# dk_binh_nuoc_nong.net
KiCad netlist of a schematic drawn in Altium Designer
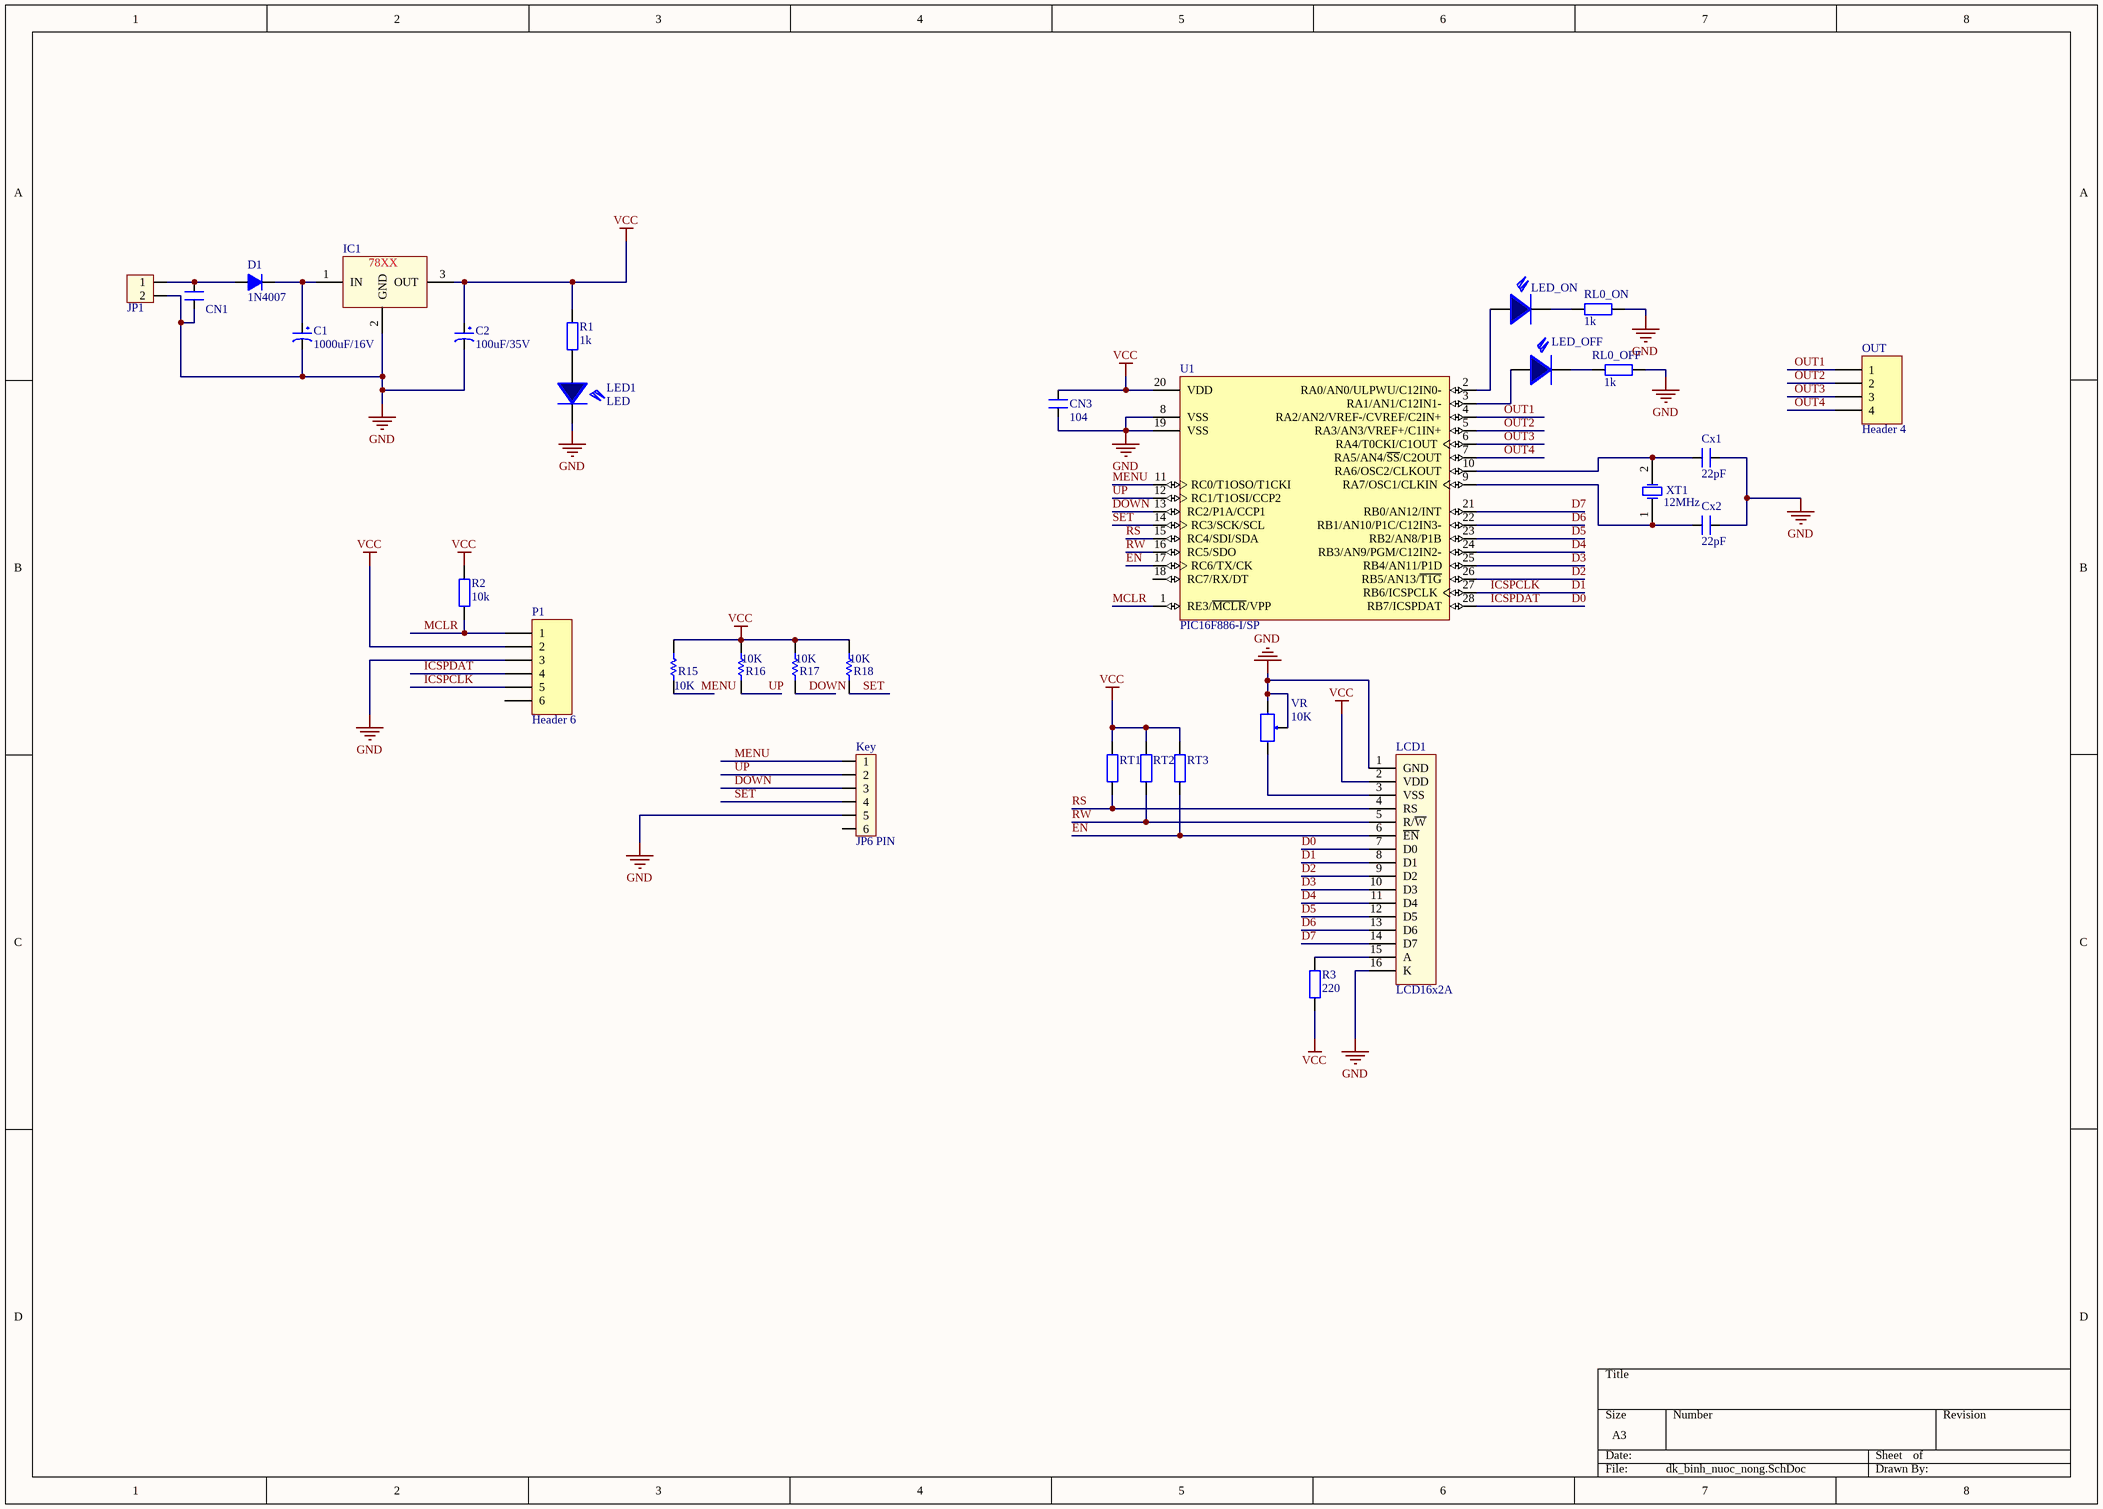
[diagram p0: dk_binh_nuoc_nong.SchDoc]

(export (version "E")
  (design (tool "Eeschema 10.0.6"))
  (components
    (comp (ref "C1")
      (value "1000uF/16V")
      (footprint "CP1.5/3.4")
      (description "Cap 1000uF/16V - 220uF/50V")
      (libsource (lib "Duy_Schematic") (part "CP4"))
    )
    (comp (ref "C2")
      (value "100uF/35V")
      (footprint "CP1.5/3.4")
      (description "Cap 100uF/35V - 470uF/16V")
      (libsource (lib "Duy_Schematic") (part "CP3"))
    )
    (comp (ref "CN1")
      (value "104")
      (footprint "CN1")
      (description "Cap np Cremic Value  104pF => 105pF")
      (libsource (lib "Duy_Schematic") (part "CN2"))
    )
    (comp (ref "CN3")
      (value "104")
      (footprint "CN1")
      (description "Cap np Cremic Value  104pF => 105pF")
      (libsource (lib "Duy_Schematic") (part "CN2"))
    )
    (comp (ref "Cx1")
      (value "22pF")
      (footprint "CN1")
      (description "Cap np Cremic value 1pF => 100pF")
      (libsource (lib "Duy_Schematic") (part "CN0"))
    )
    (comp (ref "Cx2")
      (value "22pF")
      (footprint "CN1")
      (description "Cap np Cremic value 1pF => 100pF")
      (libsource (lib "Duy_Schematic") (part "CN0"))
    )
    (comp (ref "D1")
      (value "1N4007")
      (footprint "D1A")
      (description "Diode 1A")
      (libsource (lib "Duy_Schematic") (part "D1A"))
    )
    (comp (ref "IC1") (value "78xx") (footprint "QTO-220") (libsource (lib "Duy_Schematic") (part "78xx")))
    (comp (ref "JP1")
      (value "JP2")
      (footprint "CON2")
      (description "Connector 2")
      (libsource (lib "Duy_Schematic") (part "Con2"))
    )
    (comp (ref "Key") (value "JP6 PIN") (footprint "JP6") (libsource (lib "Duy_Schematic") (part "JP6")))
    (comp (ref "LCD1")
      (value "LCD16x2A")
      (footprint "LCD16X2")
      (description "LCD dipslay 16 char, 2 line")
      (libsource (lib "Duy_Schematic") (part "LCD16x2"))
    )
    (comp (ref "LED1")
      (value "LED")
      (footprint "LED-3")
      (description "Led  Vuong")
      (libsource (lib "Duy_Schematic") (part "LED"))
    )
    (comp (ref "LED_OFF")
      (value "LED")
      (footprint "LED-3")
      (description "Led  Vuong")
      (libsource (lib "Duy_Schematic") (part "LED"))
    )
    (comp (ref "LED_ON")
      (value "LED")
      (footprint "LED-3")
      (description "Led  Vuong")
      (libsource (lib "Duy_Schematic") (part "LED"))
    )
    (comp (ref "OUT")
      (value "Header 4")
      (footprint "HDR1X4")
      (description "Header, 4-Pin")
      (fields (field (name "PUBLISHER") "Altium Limited"))
      (libsource (lib "Miscellaneous Connectors") (part "Header 4"))
    )
    (comp (ref "P1")
      (value "Header 6")
      (footprint "HED6")
      (description "Header, 6-Pin")
      (fields (field (name "PUBLISHER") "Altium Limited"))
      (libsource (lib "Miscellaneous Connectors") (part "Header 6"))
    )
    (comp (ref "R1")
      (value "1k")
      (footprint "R1/4W")
      (description "Resistor 1/4W")
      (libsource (lib "Duy_Schematic") (part "R1/4W"))
    )
    (comp (ref "R2")
      (value "10k")
      (footprint "R1/4W")
      (description "Resistor 1/4W")
      (libsource (lib "Duy_Schematic") (part "R1/4W"))
    )
    (comp (ref "R3")
      (value "220")
      (footprint "R1/4W")
      (description "Resistor 1/4W")
      (libsource (lib "Duy_Schematic") (part "R1/4W"))
    )
    (comp (ref "R15")
      (value "Res")
      (footprint "Device:R_Nor")
      (fields (field (name "ALTIUM_UNNAMED_1") "10K"))
      (libsource (lib "Device") (part "Res"))
    )
    (comp (ref "R16") (value "10K") (footprint "Device:R_Nor") (libsource (lib "Device") (part "Res")))
    (comp (ref "R17") (value "10K") (footprint "Device:R_Nor") (libsource (lib "Device") (part "Res")))
    (comp (ref "R18") (value "10K") (footprint "Device:R_Nor") (libsource (lib "Device") (part "Res")))
    (comp (ref "RL0_OFF")
      (value "1k")
      (footprint "R1/4W")
      (description "Resistor 1/4W")
      (libsource (lib "Duy_Schematic") (part "R1/4W"))
    )
    (comp (ref "RL0_ON")
      (value "1k")
      (footprint "R1/4W")
      (description "Resistor 1/4W")
      (libsource (lib "Duy_Schematic") (part "R1/4W"))
    )
    (comp (ref "RT1")
      (value "10K")
      (footprint "R1/4W")
      (description "Resistor 1/4W")
      (libsource (lib "Duy_Schematic") (part "R1/4W"))
    )
    (comp (ref "RT2")
      (value "10K")
      (footprint "R1/4W")
      (description "Resistor 1/4W")
      (libsource (lib "Duy_Schematic") (part "R1/4W"))
    )
    (comp (ref "RT3")
      (value "10K")
      (footprint "R1/4W")
      (description "Resistor 1/4W")
      (libsource (lib "Duy_Schematic") (part "R1/4W"))
    )
    (comp (ref "U1")
      (value "PIC16F886-I/SP")
      (footprint "DIP28/W0.3")
      (fields (field (name "PUBLISHER") "Altium Limited"))
      (libsource (lib "Microchip Microcontroller 8-Bit PIC16") (part "PIC16F886-I/SP"))
    )
    (comp (ref "VR")
      (value "10K")
      (footprint "VR")
      (description "Var Resistor")
      (libsource (lib "Duy_Schematic") (part "VR"))
    )
    (comp (ref "XT1")
      (value "12MHz")
      (footprint "XT2")
      (description "Crystal Oscillator")
      (fields (field (name "PUBLISHER") "Altium Limited"))
      (libsource (lib "Miscellaneous Devices") (part "XTAL"))
    )
  )
  (nets
    (net (code "1") (name "/D0") (class "Default")
      (node (ref "LCD1") (pin "7") (pinfunction "D0_7") (pintype "passive"))
      (node (ref "P1") (pin "4") (pinfunction "4_4") (pintype "passive"))
      (node (ref "U1") (pin "28") (pinfunction "RB7/ICSPDAT_28") (pintype "bidirectional"))
    )
    (net (code "2") (name "/D1") (class "Default")
      (node (ref "LCD1") (pin "8") (pinfunction "D1_8") (pintype "passive"))
      (node (ref "P1") (pin "5") (pinfunction "5_5") (pintype "passive"))
      (node (ref "U1") (pin "27") (pinfunction "RB6/ICSPCLK_27") (pintype "bidirectional"))
    )
    (net (code "3") (name "/D2") (class "Default")
      (node (ref "LCD1") (pin "9") (pinfunction "D2_9") (pintype "passive"))
      (node (ref "U1") (pin "26") (pinfunction "RB5/AN13/~{T1G}_26") (pintype "bidirectional"))
    )
    (net (code "4") (name "/D3") (class "Default")
      (node (ref "LCD1") (pin "10") (pinfunction "D3_10") (pintype "passive"))
      (node (ref "U1") (pin "25") (pinfunction "RB4/AN11/P1D_25") (pintype "bidirectional"))
    )
    (net (code "5") (name "/D4") (class "Default")
      (node (ref "LCD1") (pin "11") (pinfunction "D4_11") (pintype "passive"))
      (node (ref "U1") (pin "24") (pinfunction "RB3/AN9/PGM/C12IN2-_24") (pintype "bidirectional"))
    )
    (net (code "6") (name "/D5") (class "Default")
      (node (ref "LCD1") (pin "12") (pinfunction "D5_12") (pintype "passive"))
      (node (ref "U1") (pin "23") (pinfunction "RB2/AN8/P1B_23") (pintype "bidirectional"))
    )
    (net (code "7") (name "/D6") (class "Default")
      (node (ref "LCD1") (pin "13") (pinfunction "D6_13") (pintype "passive"))
      (node (ref "U1") (pin "22") (pinfunction "RB1/AN10/P1C/C12IN3-_22") (pintype "bidirectional"))
    )
    (net (code "8") (name "/D7") (class "Default")
      (node (ref "LCD1") (pin "14") (pinfunction "D7_14") (pintype "passive"))
      (node (ref "U1") (pin "21") (pinfunction "RB0/AN12/INT_21") (pintype "bidirectional"))
    )
    (net (code "9") (name "/DOWN") (class "Default")
      (node (ref "Key") (pin "3") (pinfunction "3_3") (pintype "passive"))
      (node (ref "R17") (pin "1") (pinfunction "1_1") (pintype "passive"))
      (node (ref "U1") (pin "13") (pinfunction "RC2/P1A/CCP1_13") (pintype "bidirectional"))
    )
    (net (code "10") (name "/EN") (class "Default")
      (node (ref "LCD1") (pin "6") (pinfunction "~{EN}_6") (pintype "passive"))
      (node (ref "RT3") (pin "2") (pinfunction "2_2") (pintype "passive"))
      (node (ref "U1") (pin "17") (pinfunction "RC6/TX/CK_17") (pintype "bidirectional"))
    )
    (net (code "11") (name "/MCLR") (class "Default")
      (node (ref "P1") (pin "1") (pinfunction "1_1") (pintype "passive"))
      (node (ref "R2") (pin "1") (pinfunction "1_1") (pintype "passive"))
      (node (ref "U1") (pin "1") (pinfunction "RE3/~{MCLR}/VPP_1") (pintype "bidirectional"))
    )
    (net (code "12") (name "/MENU") (class "Default")
      (node (ref "Key") (pin "1") (pinfunction "1_1") (pintype "passive"))
      (node (ref "R15") (pin "1") (pinfunction "1_1") (pintype "passive"))
      (node (ref "U1") (pin "11") (pinfunction "RC0/T1OSO/T1CKI_11") (pintype "bidirectional"))
    )
    (net (code "13") (name "/OUT1") (class "Default")
      (node (ref "OUT") (pin "1") (pinfunction "1_1") (pintype "passive"))
      (node (ref "U1") (pin "4") (pinfunction "RA2/AN2/VREF-/CVREF/C2IN+_4") (pintype "bidirectional"))
    )
    (net (code "14") (name "/OUT2") (class "Default")
      (node (ref "OUT") (pin "2") (pinfunction "2_2") (pintype "passive"))
      (node (ref "U1") (pin "5") (pinfunction "RA3/AN3/VREF+/C1IN+_5") (pintype "bidirectional"))
    )
    (net (code "15") (name "/OUT3") (class "Default")
      (node (ref "OUT") (pin "3") (pinfunction "3_3") (pintype "passive"))
      (node (ref "U1") (pin "6") (pinfunction "RA4/T0CKI/C1OUT_6") (pintype "bidirectional"))
    )
    (net (code "16") (name "/OUT4") (class "Default")
      (node (ref "OUT") (pin "4") (pinfunction "4_4") (pintype "passive"))
      (node (ref "U1") (pin "7") (pinfunction "RA5/AN4/~{SS}/C2OUT_7") (pintype "bidirectional"))
    )
    (net (code "17") (name "/RS") (class "Default")
      (node (ref "LCD1") (pin "4") (pinfunction "RS_4") (pintype "passive"))
      (node (ref "RT1") (pin "1") (pinfunction "1_1") (pintype "passive"))
      (node (ref "U1") (pin "15") (pinfunction "RC4/SDI/SDA_15") (pintype "bidirectional"))
    )
    (net (code "18") (name "/RW") (class "Default")
      (node (ref "LCD1") (pin "5") (pinfunction "R/~{W}_5") (pintype "passive"))
      (node (ref "RT2") (pin "1") (pinfunction "1_1") (pintype "passive"))
      (node (ref "U1") (pin "16") (pinfunction "RC5/SDO_16") (pintype "bidirectional"))
    )
    (net (code "19") (name "/SET") (class "Default")
      (node (ref "Key") (pin "4") (pinfunction "4_4") (pintype "passive"))
      (node (ref "R18") (pin "1") (pinfunction "1_1") (pintype "passive"))
      (node (ref "U1") (pin "14") (pinfunction "RC3/SCK/SCL_14") (pintype "bidirectional"))
    )
    (net (code "20") (name "/UP") (class "Default")
      (node (ref "Key") (pin "2") (pinfunction "2_2") (pintype "passive"))
      (node (ref "R16") (pin "1") (pinfunction "1_1") (pintype "passive"))
      (node (ref "U1") (pin "12") (pinfunction "RC1/T1OSI/CCP2_12") (pintype "bidirectional"))
    )
    (net (code "21") (name "GND") (class "Default")
      (node (ref "C1") (pin "2") (pinfunction "2_2") (pintype "passive"))
      (node (ref "C2") (pin "2") (pinfunction "2_2") (pintype "passive"))
      (node (ref "CN1") (pin "1") (pinfunction "1_1") (pintype "passive"))
      (node (ref "CN3") (pin "1") (pinfunction "1_1") (pintype "passive"))
      (node (ref "Cx1") (pin "2") (pinfunction "2_2") (pintype "passive"))
      (node (ref "Cx2") (pin "2") (pinfunction "2_2") (pintype "passive"))
      (node (ref "IC1") (pin "2") (pinfunction "GND_2") (pintype "passive"))
      (node (ref "JP1") (pin "2") (pinfunction "2_2") (pintype "passive"))
      (node (ref "Key") (pin "5") (pinfunction "5_5") (pintype "passive"))
      (node (ref "LCD1") (pin "1") (pinfunction "GND_1") (pintype "passive"))
      (node (ref "LCD1") (pin "16") (pinfunction "K_16") (pintype "passive"))
      (node (ref "LED1") (pin "2") (pinfunction "2_2") (pintype "passive"))
      (node (ref "P1") (pin "3") (pinfunction "3_3") (pintype "passive"))
      (node (ref "RL0_OFF") (pin "1") (pinfunction "1_1") (pintype "passive"))
      (node (ref "RL0_ON") (pin "1") (pinfunction "1_1") (pintype "passive"))
      (node (ref "U1") (pin "19") (pinfunction "VSS_19") (pintype "power_in"))
      (node (ref "U1") (pin "8") (pinfunction "VSS_8") (pintype "power_in"))
      (node (ref "VR") (pin "1") (pinfunction "1_1") (pintype "passive"))
      (node (ref "VR") (pin "2") (pinfunction "2_2") (pintype "passive"))
    )
    (net (code "22") (name "Net-(D1-A)") (class "Default")
      (node (ref "CN1") (pin "2") (pinfunction "2_2") (pintype "passive"))
      (node (ref "D1") (pin "1") (pinfunction "A_1") (pintype "passive"))
      (node (ref "JP1") (pin "1") (pinfunction "1_1") (pintype "passive"))
    )
    (net (code "23") (name "Net-(D1-K)") (class "Default")
      (node (ref "C1") (pin "1") (pinfunction "1_1") (pintype "passive"))
      (node (ref "D1") (pin "2") (pinfunction "K_2") (pintype "passive"))
      (node (ref "IC1") (pin "1") (pinfunction "IN_1") (pintype "passive"))
    )
    (net (code "24") (name "Net-(LCD1-A)") (class "Default")
      (node (ref "LCD1") (pin "15") (pinfunction "A_15") (pintype "passive"))
      (node (ref "R3") (pin "2") (pinfunction "2_2") (pintype "passive"))
    )
    (net (code "25") (name "Net-(LCD1-VSS)") (class "Default")
      (node (ref "LCD1") (pin "3") (pinfunction "VSS_3") (pintype "passive"))
      (node (ref "VR") (pin "3") (pinfunction "3_3") (pintype "passive"))
    )
    (net (code "26") (name "Net-(LED1-Pad1)") (class "Default")
      (node (ref "LED1") (pin "1") (pinfunction "1_1") (pintype "passive"))
      (node (ref "R1") (pin "1") (pinfunction "1_1") (pintype "passive"))
    )
    (net (code "27") (name "Net-(LED_OFF-Pad2)") (class "Default")
      (node (ref "LED_OFF") (pin "2") (pinfunction "2_2") (pintype "passive"))
      (node (ref "RL0_OFF") (pin "2") (pinfunction "2_2") (pintype "passive"))
    )
    (net (code "28") (name "Net-(LED_ON-Pad2)") (class "Default")
      (node (ref "LED_ON") (pin "2") (pinfunction "2_2") (pintype "passive"))
      (node (ref "RL0_ON") (pin "2") (pinfunction "2_2") (pintype "passive"))
    )
    (net (code "29") (name "Net-(U1-RA0{slash}AN0{slash}ULPWU{slash}C12IN0-)") (class "Default")
      (node (ref "LED_ON") (pin "1") (pinfunction "1_1") (pintype "passive"))
      (node (ref "U1") (pin "2") (pinfunction "RA0/AN0/ULPWU/C12IN0-_2") (pintype "bidirectional"))
    )
    (net (code "30") (name "Net-(U1-RA1{slash}AN1{slash}C12IN1-)") (class "Default")
      (node (ref "LED_OFF") (pin "1") (pinfunction "1_1") (pintype "passive"))
      (node (ref "U1") (pin "3") (pinfunction "RA1/AN1/C12IN1-_3") (pintype "bidirectional"))
    )
    (net (code "31") (name "Net-(U1-RA6{slash}OSC2{slash}CLKOUT)") (class "Default")
      (node (ref "Cx1") (pin "1") (pinfunction "1_1") (pintype "passive"))
      (node (ref "U1") (pin "10") (pinfunction "RA6/OSC2/CLKOUT_10") (pintype "bidirectional"))
      (node (ref "XT1") (pin "2") (pinfunction "OSC2_2") (pintype "passive"))
    )
    (net (code "32") (name "Net-(U1-RA7{slash}OSC1{slash}CLKIN)") (class "Default")
      (node (ref "Cx2") (pin "1") (pinfunction "1_1") (pintype "passive"))
      (node (ref "U1") (pin "9") (pinfunction "RA7/OSC1/CLKIN_9") (pintype "bidirectional"))
      (node (ref "XT1") (pin "1") (pinfunction "OSC1_1") (pintype "passive"))
    )
    (net (code "33") (name "VCC") (class "Default")
      (node (ref "C2") (pin "1") (pinfunction "1_1") (pintype "passive"))
      (node (ref "CN3") (pin "2") (pinfunction "2_2") (pintype "passive"))
      (node (ref "IC1") (pin "3") (pinfunction "OUT_3") (pintype "passive"))
      (node (ref "LCD1") (pin "2") (pinfunction "VDD_2") (pintype "passive"))
      (node (ref "P1") (pin "2") (pinfunction "2_2") (pintype "passive"))
      (node (ref "R1") (pin "2") (pinfunction "2_2") (pintype "passive"))
      (node (ref "R15") (pin "2") (pinfunction "2_2") (pintype "passive"))
      (node (ref "R16") (pin "2") (pinfunction "2_2") (pintype "passive"))
      (node (ref "R17") (pin "2") (pinfunction "2_2") (pintype "passive"))
      (node (ref "R18") (pin "2") (pinfunction "2_2") (pintype "passive"))
      (node (ref "R2") (pin "2") (pinfunction "2_2") (pintype "passive"))
      (node (ref "R3") (pin "1") (pinfunction "1_1") (pintype "passive"))
      (node (ref "RT1") (pin "2") (pinfunction "2_2") (pintype "passive"))
      (node (ref "RT2") (pin "2") (pinfunction "2_2") (pintype "passive"))
      (node (ref "RT3") (pin "1") (pinfunction "1_1") (pintype "passive"))
      (node (ref "U1") (pin "20") (pinfunction "VDD_20") (pintype "power_in"))
    )
    (net (code "34") (name "unconnected-(Key-Pad6)") (class "Default")
      (node (ref "Key") (pin "6") (pinfunction "6_6") (pintype "passive"))
    )
    (net (code "35") (name "unconnected-(P1-Pad6)") (class "Default")
      (node (ref "P1") (pin "6") (pinfunction "6_6") (pintype "passive"))
    )
    (net (code "36") (name "unconnected-(U1-RC7{slash}RX{slash}DT-Pad18)") (class "Default")
      (node (ref "U1") (pin "18") (pinfunction "RC7/RX/DT_18") (pintype "bidirectional"))
    )
  )
)
